# Connectors.net
KiCad netlist of a schematic drawn in Altium Designer
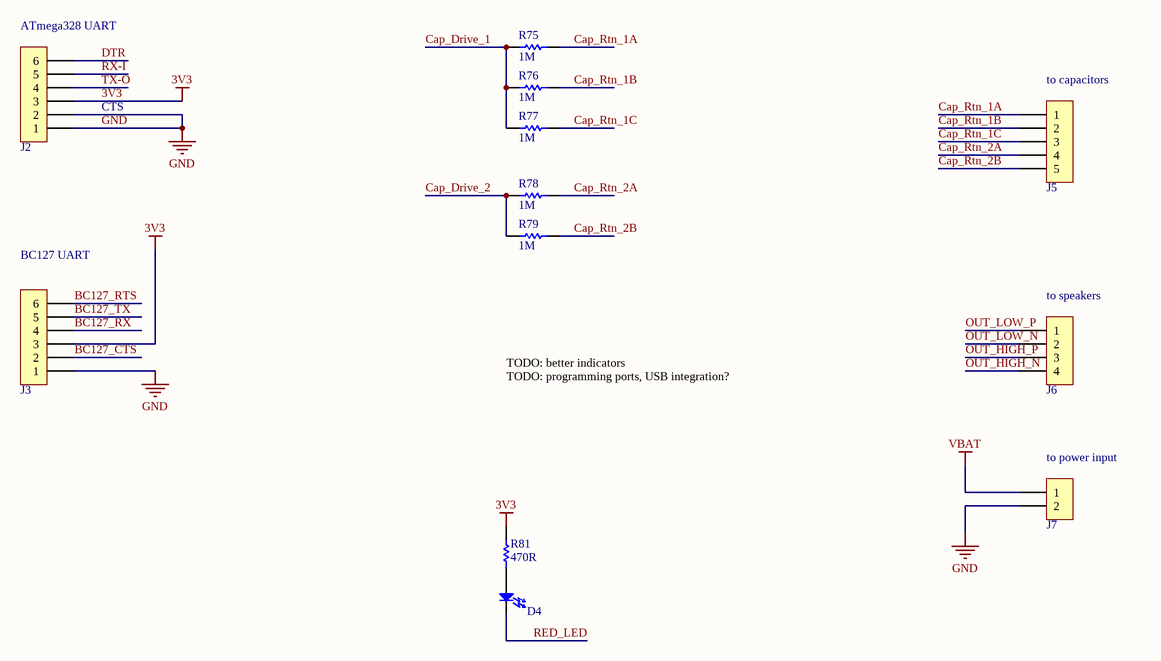
[diagram p0: Connectors.SchDoc]

(export (version "E")
  (design (tool "Eeschema 10.0.6"))
  (components
    (comp (ref "D4")
      (value "LED 0603")
      (footprint "DIOM1608X08N")
      (fields (field (name "VOLTAGE") "2.2V") (field (name "DIGIKEY PART NUMBER") "160-1447-1-ND"))
      (libsource (lib "Speaker Library") (part "LED 0603"))
    )
    (comp (ref "J2")
      (value "6POS THRU HOLE 2.54MM")
      (footprint "90147-1106")
      (libsource (lib "Speaker Library") (part "6POS THRU HOLE 2.54MM"))
    )
    (comp (ref "J3")
      (value "6POS THRU HOLE 2.54MM")
      (footprint "90147-1106")
      (libsource (lib "Speaker Library") (part "6POS THRU HOLE 2.54MM"))
    )
    (comp (ref "J5")
      (value "5POS THRU HOLE 2.54MM")
      (footprint "70543-0004")
      (libsource (lib "Speaker Library") (part "5POS THRU HOLE 2.54MM"))
    )
    (comp (ref "J6")
      (value "TERMINAL BLOCK 4POS")
      (footprint "TERMINAL BLOCK 5MM 4POS")
      (fields (field (name "DIGIKEY PART NUMBER") "ED2563-ND"))
      (libsource (lib "Speaker Library") (part "TERMINAL BLOCK 4POS"))
    )
    (comp (ref "J7")
      (value "TERMINAL BLOCK 2POS")
      (footprint "TERMINAL BLOCK 5MM 2POS")
      (fields (field (name "DIGIKEY PART NUMBER") "ED2561-ND"))
      (libsource (lib "Speaker Library") (part "TERMINAL BLOCK 2POS"))
    )
    (comp (ref "R75")
      (value "1M")
      (footprint "RESC1608X06N")
      (fields
        (field (name "TOLERANCE") "1%")
        (field (name "POWER") "0.1W")
        (field (name "DIGIKEY PART NUMBER") "311-1.00MHRCT-ND")
      )
      (libsource (lib "Speaker Library") (part "RES 1M 0603"))
    )
    (comp (ref "R76")
      (value "1M")
      (footprint "RESC1608X06N")
      (fields
        (field (name "TOLERANCE") "1%")
        (field (name "POWER") "0.1W")
        (field (name "DIGIKEY PART NUMBER") "311-1.00MHRCT-ND")
      )
      (libsource (lib "Speaker Library") (part "RES 1M 0603"))
    )
    (comp (ref "R77")
      (value "1M")
      (footprint "RESC1608X06N")
      (fields
        (field (name "TOLERANCE") "1%")
        (field (name "POWER") "0.1W")
        (field (name "DIGIKEY PART NUMBER") "311-1.00MHRCT-ND")
      )
      (libsource (lib "Speaker Library") (part "RES 1M 0603"))
    )
    (comp (ref "R78")
      (value "1M")
      (footprint "RESC1608X06N")
      (fields
        (field (name "TOLERANCE") "1%")
        (field (name "POWER") "0.1W")
        (field (name "DIGIKEY PART NUMBER") "311-1.00MHRCT-ND")
      )
      (libsource (lib "Speaker Library") (part "RES 1M 0603"))
    )
    (comp (ref "R79")
      (value "1M")
      (footprint "RESC1608X06N")
      (fields
        (field (name "TOLERANCE") "1%")
        (field (name "POWER") "0.1W")
        (field (name "DIGIKEY PART NUMBER") "311-1.00MHRCT-ND")
      )
      (libsource (lib "Speaker Library") (part "RES 1M 0603"))
    )
    (comp (ref "R81")
      (value "470R")
      (footprint "RESC1608X06N")
      (fields
        (field (name "TOLERANCE") "1%")
        (field (name "POWER") "0.25W")
        (field (name "DIGIKEY PART NUMBER") "311-470HRCT-ND")
      )
      (libsource (lib "Speaker Library") (part "RES 470R 0603"))
    )
  )
  (nets
    (net (code "1") (name "/BC127_CTS") (class "Default")
      (node (ref "J3") (pin "2") (pinfunction "2_2") (pintype "passive"))
    )
    (net (code "2") (name "/BC127_RTS") (class "Default")
      (node (ref "J3") (pin "6") (pinfunction "6_6") (pintype "passive"))
    )
    (net (code "3") (name "/BC127_RX") (class "Default")
      (node (ref "J3") (pin "4") (pinfunction "4_4") (pintype "passive"))
    )
    (net (code "4") (name "/BC127_TX") (class "Default")
      (node (ref "J3") (pin "5") (pinfunction "5_5") (pintype "passive"))
    )
    (net (code "5") (name "/Cap_Drive_1") (class "Default")
      (node (ref "R75") (pin "1") (pinfunction "1_1") (pintype "passive"))
      (node (ref "R76") (pin "1") (pinfunction "1_1") (pintype "passive"))
      (node (ref "R77") (pin "1") (pinfunction "1_1") (pintype "passive"))
    )
    (net (code "6") (name "/Cap_Drive_2") (class "Default")
      (node (ref "R78") (pin "1") (pinfunction "1_1") (pintype "passive"))
      (node (ref "R79") (pin "1") (pinfunction "1_1") (pintype "passive"))
    )
    (net (code "7") (name "/Cap_Rtn_1A") (class "Default")
      (node (ref "J5") (pin "1") (pinfunction "1_1") (pintype "passive"))
      (node (ref "R75") (pin "2") (pinfunction "2_2") (pintype "passive"))
    )
    (net (code "8") (name "/Cap_Rtn_1B") (class "Default")
      (node (ref "J5") (pin "2") (pinfunction "2_2") (pintype "passive"))
      (node (ref "R76") (pin "2") (pinfunction "2_2") (pintype "passive"))
    )
    (net (code "9") (name "/Cap_Rtn_1C") (class "Default")
      (node (ref "J5") (pin "3") (pinfunction "3_3") (pintype "passive"))
      (node (ref "R77") (pin "2") (pinfunction "2_2") (pintype "passive"))
    )
    (net (code "10") (name "/Cap_Rtn_2A") (class "Default")
      (node (ref "J5") (pin "4") (pinfunction "4_4") (pintype "passive"))
      (node (ref "R78") (pin "2") (pinfunction "2_2") (pintype "passive"))
    )
    (net (code "11") (name "/Cap_Rtn_2B") (class "Default")
      (node (ref "J5") (pin "5") (pinfunction "5_5") (pintype "passive"))
      (node (ref "R79") (pin "2") (pinfunction "2_2") (pintype "passive"))
    )
    (net (code "12") (name "/DTR") (class "Default")
      (node (ref "J2") (pin "6") (pinfunction "6_6") (pintype "passive"))
    )
    (net (code "13") (name "/OUT_HIGH_N") (class "Default")
      (node (ref "J6") (pin "4") (pinfunction "4_4") (pintype "passive"))
    )
    (net (code "14") (name "/OUT_HIGH_P") (class "Default")
      (node (ref "J6") (pin "3") (pinfunction "3_3") (pintype "passive"))
    )
    (net (code "15") (name "/OUT_LOW_N") (class "Default")
      (node (ref "J6") (pin "2") (pinfunction "2_2") (pintype "passive"))
    )
    (net (code "16") (name "/OUT_LOW_P") (class "Default")
      (node (ref "J6") (pin "1") (pinfunction "1_1") (pintype "passive"))
    )
    (net (code "17") (name "/RED_LED") (class "Default")
      (node (ref "D4") (pin "1") (pinfunction "K2_1") (pintype "passive"))
    )
    (net (code "18") (name "/RX-I") (class "Default")
      (node (ref "J2") (pin "5") (pinfunction "5_5") (pintype "passive"))
    )
    (net (code "19") (name "/TX-O") (class "Default")
      (node (ref "J2") (pin "4") (pinfunction "4_4") (pintype "passive"))
    )
    (net (code "20") (name "3V3") (class "Default")
      (node (ref "J2") (pin "3") (pinfunction "3_3") (pintype "passive"))
      (node (ref "J3") (pin "3") (pinfunction "3_3") (pintype "passive"))
      (node (ref "R81") (pin "2") (pinfunction "2_2") (pintype "passive"))
    )
    (net (code "21") (name "GND") (class "Default")
      (node (ref "J2") (pin "1") (pinfunction "1_1") (pintype "passive"))
      (node (ref "J2") (pin "2") (pinfunction "2_2") (pintype "passive"))
      (node (ref "J3") (pin "1") (pinfunction "1_1") (pintype "passive"))
      (node (ref "J7") (pin "2") (pinfunction "2_2") (pintype "passive"))
    )
    (net (code "22") (name "Net-(D4-A2)") (class "Default")
      (node (ref "D4") (pin "2") (pinfunction "A2_2") (pintype "passive"))
      (node (ref "R81") (pin "1") (pinfunction "1_1") (pintype "passive"))
    )
    (net (code "23") (name "VBAT") (class "Default")
      (node (ref "J7") (pin "1") (pinfunction "1_1") (pintype "passive"))
    )
  )
)
